# TiltyDuo.net
KiCad netlist of a schematic drawn in EAGLE
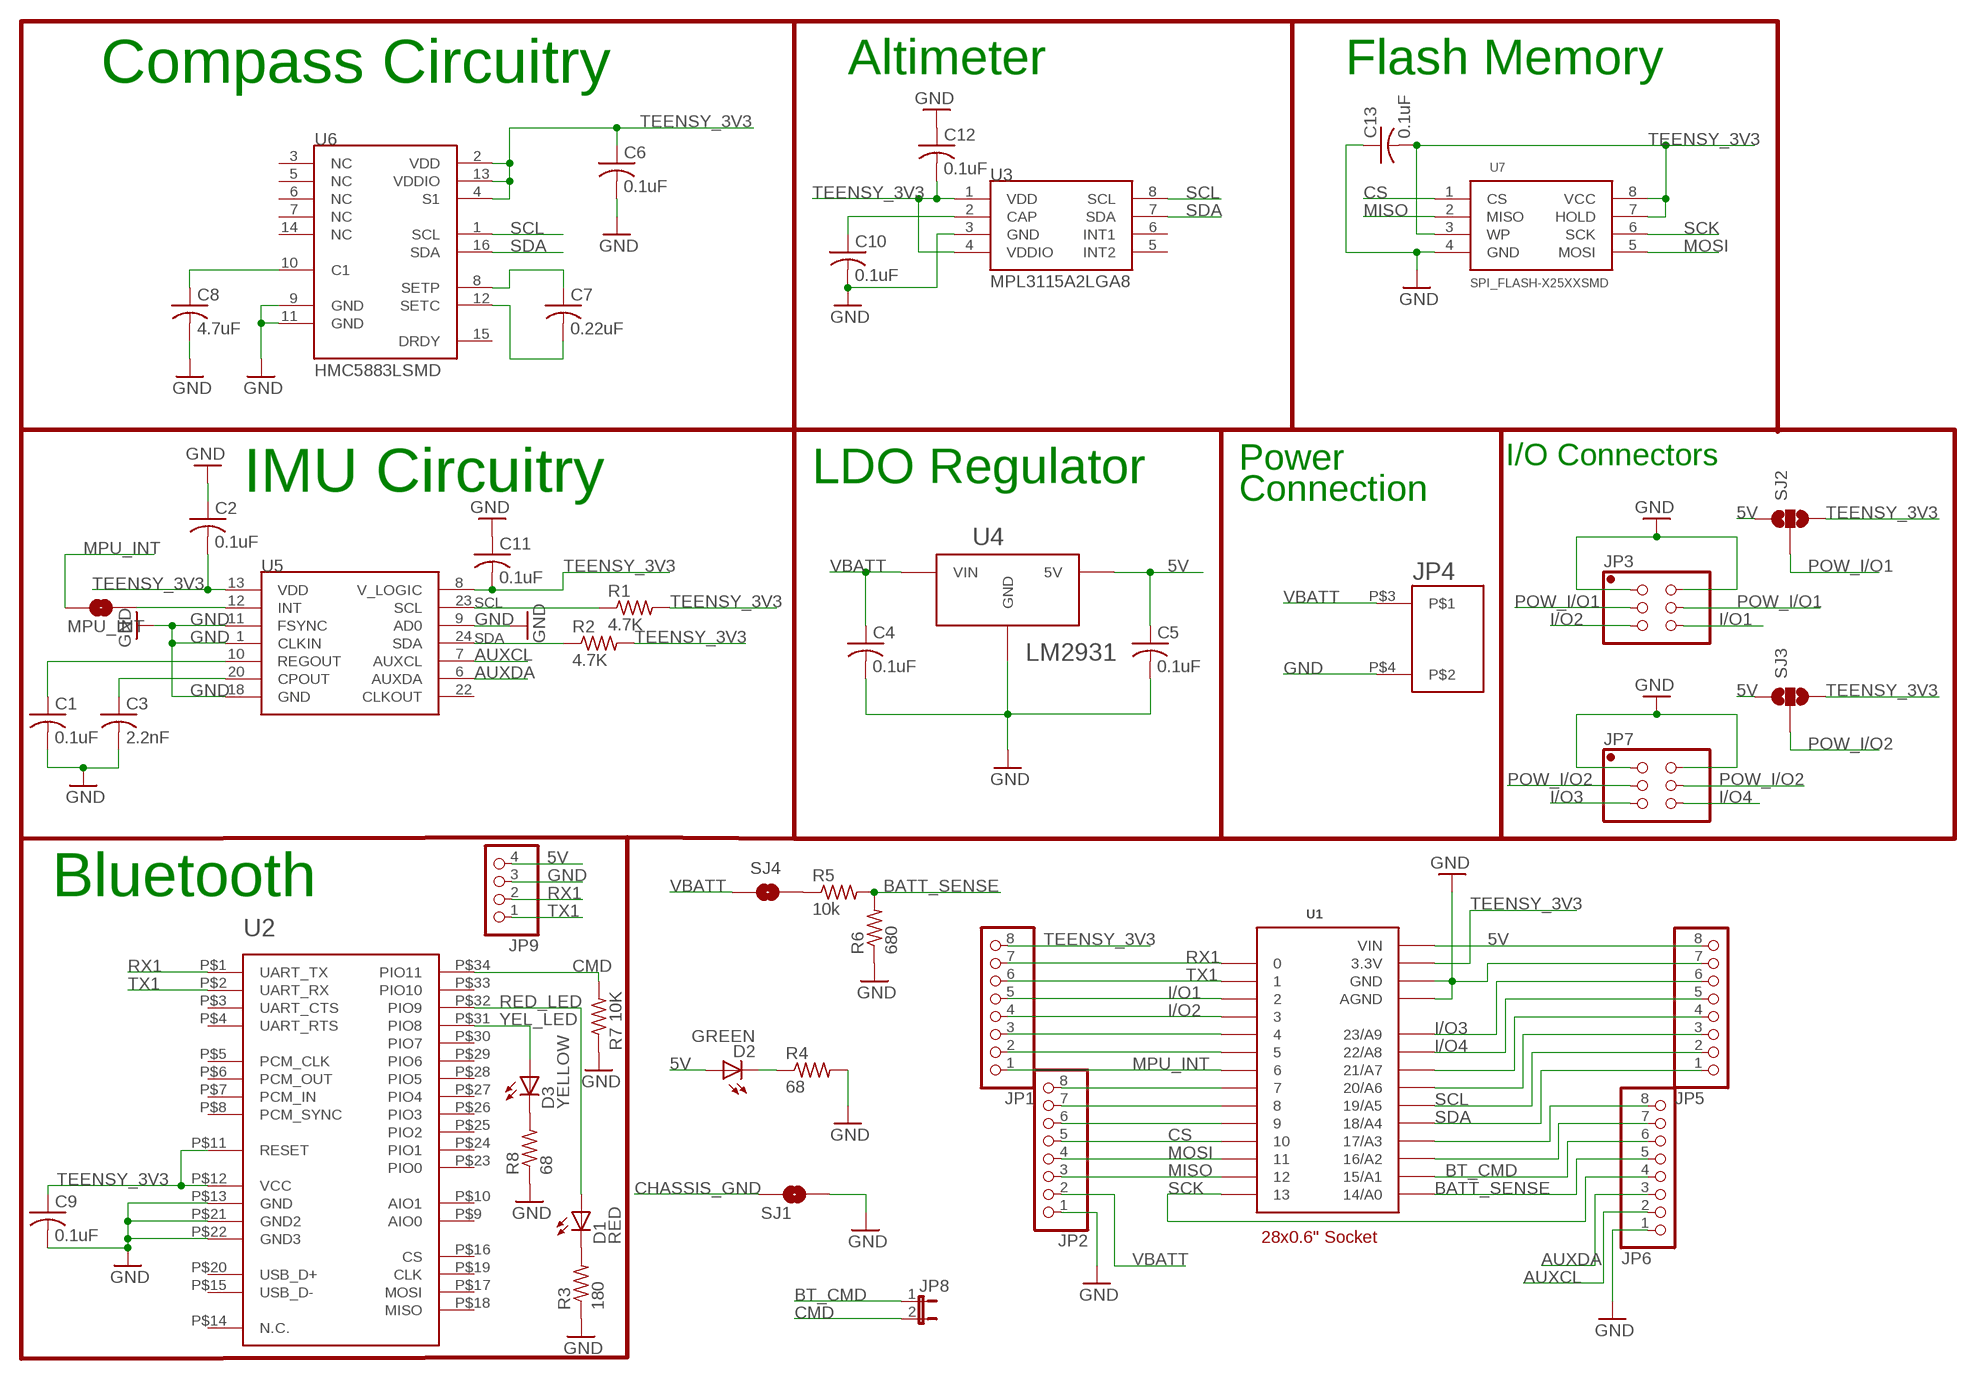
[diagram p0: schematic, sheet 1]

(export (version "E")
  (design (tool "Eeschema 10.0.6"))
  (components
    (comp (ref "C1")
      (value "0.1uF")
      (footprint "eagle-import:C0603")
      (libsource (lib "eagle-import") (part "C-USC0603"))
    )
    (comp (ref "C2")
      (value "0.1uF")
      (footprint "eagle-import:C0603")
      (libsource (lib "eagle-import") (part "C-USC0603"))
    )
    (comp (ref "C3")
      (value "2.2nF")
      (footprint "eagle-import:C0603")
      (libsource (lib "eagle-import") (part "C-USC0603"))
    )
    (comp (ref "C4")
      (value "0.1uF")
      (footprint "eagle-import:C0603")
      (libsource (lib "eagle-import") (part "C-USC0603"))
    )
    (comp (ref "C5")
      (value "0.1uF")
      (footprint "eagle-import:C0603")
      (libsource (lib "eagle-import") (part "C-USC0603"))
    )
    (comp (ref "C6")
      (value "0.1uF")
      (footprint "eagle-import:C0603")
      (libsource (lib "eagle-import") (part "C-USC0603"))
    )
    (comp (ref "C7")
      (value "0.22uF")
      (footprint "eagle-import:C0603")
      (libsource (lib "eagle-import") (part "C-USC0603"))
    )
    (comp (ref "C8")
      (value "4.7uF")
      (footprint "eagle-import:C0603")
      (libsource (lib "eagle-import") (part "C-USC0603"))
    )
    (comp (ref "C9")
      (value "0.1uF")
      (footprint "eagle-import:C0603")
      (libsource (lib "eagle-import") (part "C-USC0603"))
    )
    (comp (ref "C10")
      (value "0.1uF")
      (footprint "eagle-import:C0603")
      (libsource (lib "eagle-import") (part "C-USC0603"))
    )
    (comp (ref "C11")
      (value "0.1uF")
      (footprint "eagle-import:C0603")
      (libsource (lib "eagle-import") (part "C-USC0603"))
    )
    (comp (ref "C12")
      (value "0.1uF")
      (footprint "eagle-import:C0603")
      (libsource (lib "eagle-import") (part "C-USC0603"))
    )
    (comp (ref "C13")
      (value "0.1uF")
      (footprint "eagle-import:C0603")
      (libsource (lib "eagle-import") (part "C-USC0603"))
    )
    (comp (ref "D1")
      (value "RED")
      (footprint "eagle-import:LED-0805")
      (libsource (lib "eagle-import") (part "LED-GREENLED-0805_NO_SILK"))
    )
    (comp (ref "D2")
      (value "GREEN")
      (footprint "eagle-import:LED-0805")
      (libsource (lib "eagle-import") (part "LED-GREENLED-0805_NO_SILK"))
    )
    (comp (ref "D3")
      (value "YELLOW")
      (footprint "eagle-import:LED-0805")
      (libsource (lib "eagle-import") (part "LED-GREENLED-0805_NO_SILK"))
    )
    (comp (ref "JP1")
      (value "PINHD-1X81X08_NO_SILK_LOCK")
      (footprint "eagle-import:1X08_NO_SS_LOCKING")
      (libsource (lib "eagle-import") (part "PINHD-1X81X08_NO_SILK_LOCK"))
    )
    (comp (ref "JP2")
      (value "PINHD-1X81X08_NO_SILK_LOCK")
      (footprint "eagle-import:1X08_NO_SS_LOCKING")
      (libsource (lib "eagle-import") (part "PINHD-1X81X08_NO_SILK_LOCK"))
    )
    (comp (ref "JP3")
      (value "PINHD-2X32X03_NO_SS_LOCK")
      (footprint "eagle-import:2X03_NO_SS_LOCK")
      (libsource (lib "eagle-import") (part "PINHD-2X32X03_NO_SS_LOCK"))
    )
    (comp (ref "JP4")
      (value "2-POS_SMD_TERM_BLOCK")
      (footprint "eagle-import:2-POS_SMD_TERMINAL_BLOCK")
      (libsource (lib "eagle-import") (part "2-POS_SMD_TERM_BLOCK"))
    )
    (comp (ref "JP5")
      (value "PINHD-1X81X08_NO_SILK_LOCK")
      (footprint "eagle-import:1X08_NO_SS_LOCKING")
      (libsource (lib "eagle-import") (part "PINHD-1X81X08_NO_SILK_LOCK"))
    )
    (comp (ref "JP6")
      (value "PINHD-1X81X08_NO_SILK_LOCK")
      (footprint "eagle-import:1X08_NO_SS_LOCKING")
      (libsource (lib "eagle-import") (part "PINHD-1X81X08_NO_SILK_LOCK"))
    )
    (comp (ref "JP7")
      (value "PINHD-2X32X03_NO_SS_LOCK")
      (footprint "eagle-import:2X03_NO_SS_LOCK")
      (libsource (lib "eagle-import") (part "PINHD-2X32X03_NO_SS_LOCK"))
    )
    (comp (ref "JP8")
      (value "JUMPER-2SMD-NC")
      (footprint "eagle-import:SJ_2S")
      (libsource (lib "eagle-import") (part "JUMPER-2SMD-NC"))
    )
    (comp (ref "JP9")
      (value "PINHD-1X41X04_NO_SS_LOCKING")
      (footprint "eagle-import:1X04_NO_SS_LOCKING")
      (libsource (lib "eagle-import") (part "PINHD-1X41X04_NO_SS_LOCKING"))
    )
    (comp (ref "MPU_INT")
      (value "SOLDERJUMPERNO")
      (footprint "eagle-import:SJ_2S-NO")
      (libsource (lib "eagle-import") (part "SOLDERJUMPERNO"))
    )
    (comp (ref "R1")
      (value "4.7K")
      (footprint "eagle-import:R0603")
      (libsource (lib "eagle-import") (part "R-US_R0603"))
    )
    (comp (ref "R2")
      (value "4.7K")
      (footprint "eagle-import:R0603")
      (libsource (lib "eagle-import") (part "R-US_R0603"))
    )
    (comp (ref "R3")
      (value "180")
      (footprint "eagle-import:R0603")
      (libsource (lib "eagle-import") (part "R-US_R0603"))
    )
    (comp (ref "R4")
      (value "68")
      (footprint "eagle-import:R0603")
      (libsource (lib "eagle-import") (part "R-US_R0603"))
    )
    (comp (ref "R5")
      (value "10k")
      (footprint "eagle-import:R0603")
      (libsource (lib "eagle-import") (part "R-US_R0603"))
    )
    (comp (ref "R6")
      (value "680")
      (footprint "eagle-import:R0603")
      (libsource (lib "eagle-import") (part "R-US_R0603"))
    )
    (comp (ref "R7")
      (value "10K")
      (footprint "eagle-import:R0603")
      (libsource (lib "eagle-import") (part "R-US_R0603"))
    )
    (comp (ref "R8")
      (value "68")
      (footprint "eagle-import:R0603")
      (libsource (lib "eagle-import") (part "R-US_R0603"))
    )
    (comp (ref "SJ1")
      (value "SOLDERJUMPERNO")
      (footprint "eagle-import:SJ_2S-NO")
      (libsource (lib "eagle-import") (part "SOLDERJUMPERNO"))
    )
    (comp (ref "SJ2")
      (value "SOLDERJUMPER_2WAYS")
      (footprint "eagle-import:SJ_3")
      (libsource (lib "eagle-import") (part "SOLDERJUMPER_2WAYS"))
    )
    (comp (ref "SJ3")
      (value "SOLDERJUMPER_2WAYS")
      (footprint "eagle-import:SJ_3")
      (libsource (lib "eagle-import") (part "SOLDERJUMPER_2WAYS"))
    )
    (comp (ref "SJ4")
      (value "SOLDERJUMPERTRACE")
      (footprint "eagle-import:SJ_2S-TRACE")
      (libsource (lib "eagle-import") (part "SOLDERJUMPERTRACE"))
    )
    (comp (ref "U1")
      (value "TEENSY_3.0_OUTER-PINS28-DIP_SOCKET")
      (footprint "eagle-import:28-DIP")
      (libsource (lib "eagle-import") (part "TEENSY_3.0_OUTER-PINS28-DIP_SOCKET"))
    )
    (comp (ref "U2")
      (value "HC-09_BREAKOUT")
      (footprint "eagle-import:HC-09_BREAKOUT")
      (libsource (lib "eagle-import") (part "HC-09_BREAKOUT"))
    )
    (comp (ref "U3")
      (value "MPL3115A2LGA8")
      (footprint "eagle-import:LGA8")
      (libsource (lib "eagle-import") (part "MPL3115A2LGA8"))
    )
    (comp (ref "U4")
      (value "LM2931")
      (footprint "eagle-import:TO263")
      (libsource (lib "eagle-import") (part "LM2931"))
    )
    (comp (ref "U5")
      (value "MPU-6050")
      (footprint "eagle-import:QFN-24")
      (libsource (lib "eagle-import") (part "MPU-6050"))
    )
    (comp (ref "U6")
      (value "HMC5883LSMD")
      (footprint "eagle-import:16LPCC")
      (libsource (lib "eagle-import") (part "HMC5883LSMD"))
    )
    (comp (ref "U7")
      (value "SPI_FLASH-X25XXSMD")
      (footprint "eagle-import:SO08")
      (fields (field (name "PART#") "S25FL204K0TMFI011"))
      (libsource (lib "eagle-import") (part "SPI_FLASH-X25XXSMD"))
    )
  )
  (nets
    (net (code "1") (name "/5V") (class "Default")
      (node (ref "C5") (pin "1") (pinfunction "1_1") (pintype "passive"))
      (node (ref "D2") (pin "1") (pinfunction "A_1") (pintype "passive"))
      (node (ref "JP5") (pin "8") (pinfunction "8_8") (pintype "passive"))
      (node (ref "JP9") (pin "4") (pinfunction "4_4") (pintype "passive"))
      (node (ref "SJ2") (pin "1") (pinfunction "1_1") (pintype "passive"))
      (node (ref "SJ3") (pin "1") (pinfunction "1_1") (pintype "passive"))
      (node (ref "U1") (pin "P$15") (pinfunction "VIN_P$15") (pintype "power_in"))
      (node (ref "U4") (pin "P$3") (pinfunction "5V_P$3") (pintype "bidirectional"))
    )
    (net (code "2") (name "/AUXCL") (class "Default")
      (node (ref "JP6") (pin "2") (pinfunction "2_2") (pintype "passive"))
      (node (ref "U5") (pin "7") (pinfunction "AUXCL_7") (pintype "bidirectional"))
    )
    (net (code "3") (name "/AUXDA") (class "Default")
      (node (ref "JP6") (pin "3") (pinfunction "3_3") (pintype "passive"))
      (node (ref "U5") (pin "6") (pinfunction "AUXDA_6") (pintype "bidirectional"))
    )
    (net (code "4") (name "/BATT_SENSE") (class "Default")
      (node (ref "JP6") (pin "5") (pinfunction "5_5") (pintype "passive"))
      (node (ref "R5") (pin "2") (pinfunction "2_2") (pintype "passive"))
      (node (ref "R6") (pin "2") (pinfunction "2_2") (pintype "passive"))
      (node (ref "U1") (pin "P$27") (pinfunction "14/A0_P$27") (pintype "bidirectional"))
    )
    (net (code "5") (name "/BT_CMD") (class "Default")
      (node (ref "JP6") (pin "6") (pinfunction "6_6") (pintype "passive"))
      (node (ref "JP8") (pin "1") (pinfunction "1_1") (pintype "passive"))
      (node (ref "U1") (pin "P$26") (pinfunction "15/A1_P$26") (pintype "bidirectional"))
    )
    (net (code "6") (name "/CHASSIS_GND") (class "Default")
      (node (ref "SJ1") (pin "1") (pinfunction "1_1") (pintype "passive"))
    )
    (net (code "7") (name "/CMD") (class "Default")
      (node (ref "JP8") (pin "2") (pinfunction "2_2") (pintype "passive"))
      (node (ref "R7") (pin "2") (pinfunction "2_2") (pintype "passive"))
      (node (ref "U2") (pin "P$34") (pinfunction "PIO11_P$34") (pintype "bidirectional"))
    )
    (net (code "8") (name "/CS") (class "Default")
      (node (ref "JP2") (pin "5") (pinfunction "5_5") (pintype "passive"))
      (node (ref "U1") (pin "P$12") (pinfunction "10_P$12") (pintype "bidirectional"))
      (node (ref "U7") (pin "1") (pinfunction "CS_1") (pintype "bidirectional"))
    )
    (net (code "9") (name "/I{slash}O1") (class "Default")
      (node (ref "JP1") (pin "5") (pinfunction "5_5") (pintype "passive"))
      (node (ref "JP3") (pin "6") (pinfunction "6_6") (pintype "passive"))
      (node (ref "U1") (pin "P$4") (pinfunction "2_P$4") (pintype "bidirectional"))
    )
    (net (code "10") (name "/I{slash}O2") (class "Default")
      (node (ref "JP1") (pin "4") (pinfunction "4_4") (pintype "passive"))
      (node (ref "JP3") (pin "5") (pinfunction "5_5") (pintype "passive"))
      (node (ref "U1") (pin "P$5") (pinfunction "3_P$5") (pintype "bidirectional"))
    )
    (net (code "11") (name "/I{slash}O3") (class "Default")
      (node (ref "JP5") (pin "6") (pinfunction "6_6") (pintype "passive"))
      (node (ref "JP7") (pin "5") (pinfunction "5_5") (pintype "passive"))
      (node (ref "U1") (pin "P$18") (pinfunction "23/A9_P$18") (pintype "bidirectional"))
    )
    (net (code "12") (name "/I{slash}O4") (class "Default")
      (node (ref "JP5") (pin "5") (pinfunction "5_5") (pintype "passive"))
      (node (ref "JP7") (pin "6") (pinfunction "6_6") (pintype "passive"))
      (node (ref "U1") (pin "P$19") (pinfunction "22/A8_P$19") (pintype "bidirectional"))
    )
    (net (code "13") (name "/MISO") (class "Default")
      (node (ref "JP2") (pin "3") (pinfunction "3_3") (pintype "passive"))
      (node (ref "U1") (pin "P$14") (pinfunction "12_P$14") (pintype "bidirectional"))
      (node (ref "U7") (pin "2") (pinfunction "MISO_2") (pintype "bidirectional"))
    )
    (net (code "14") (name "/MOSI") (class "Default")
      (node (ref "JP2") (pin "4") (pinfunction "4_4") (pintype "passive"))
      (node (ref "U1") (pin "P$13") (pinfunction "11_P$13") (pintype "bidirectional"))
      (node (ref "U7") (pin "5") (pinfunction "MOSI_5") (pintype "bidirectional"))
    )
    (net (code "15") (name "/MPU_INT") (class "Default")
      (node (ref "JP1") (pin "1") (pinfunction "1_1") (pintype "passive"))
      (node (ref "MPU_INT") (pin "1") (pinfunction "1_1") (pintype "passive"))
      (node (ref "U1") (pin "P$8") (pinfunction "6_P$8") (pintype "bidirectional"))
    )
    (net (code "16") (name "/POW_I{slash}O1") (class "Default")
      (node (ref "JP3") (pin "3") (pinfunction "3_3") (pintype "passive"))
      (node (ref "JP3") (pin "4") (pinfunction "4_4") (pintype "passive"))
      (node (ref "SJ2") (pin "2") (pinfunction "2_2") (pintype "passive"))
    )
    (net (code "17") (name "/POW_I{slash}O2") (class "Default")
      (node (ref "JP7") (pin "3") (pinfunction "3_3") (pintype "passive"))
      (node (ref "JP7") (pin "4") (pinfunction "4_4") (pintype "passive"))
      (node (ref "SJ3") (pin "2") (pinfunction "2_2") (pintype "passive"))
    )
    (net (code "18") (name "/RED_LED") (class "Default")
      (node (ref "D1") (pin "1") (pinfunction "A_1") (pintype "passive"))
      (node (ref "U2") (pin "P$32") (pinfunction "PIO9_P$32") (pintype "bidirectional"))
    )
    (net (code "19") (name "/RX1") (class "Default")
      (node (ref "JP1") (pin "7") (pinfunction "7_7") (pintype "passive"))
      (node (ref "JP9") (pin "2") (pinfunction "2_2") (pintype "passive"))
      (node (ref "U1") (pin "P$2") (pinfunction "0_P$2") (pintype "bidirectional"))
      (node (ref "U2") (pin "P$1") (pinfunction "UART_TX_P$1") (pintype "bidirectional"))
    )
    (net (code "20") (name "/SCK") (class "Default")
      (node (ref "JP6") (pin "4") (pinfunction "4_4") (pintype "passive"))
      (node (ref "U1") (pin "P$28") (pinfunction "13_P$28") (pintype "bidirectional"))
      (node (ref "U7") (pin "6") (pinfunction "SCK_6") (pintype "bidirectional"))
    )
    (net (code "21") (name "/SCL") (class "Default")
      (node (ref "JP5") (pin "2") (pinfunction "2_2") (pintype "passive"))
      (node (ref "R1") (pin "1") (pinfunction "1_1") (pintype "passive"))
      (node (ref "U1") (pin "P$22") (pinfunction "19/A5_P$22") (pintype "bidirectional"))
      (node (ref "U3") (pin "8") (pinfunction "SCL_8") (pintype "bidirectional"))
      (node (ref "U5") (pin "23") (pinfunction "SCL_23") (pintype "bidirectional"))
      (node (ref "U6") (pin "1") (pinfunction "SCL_1") (pintype "bidirectional"))
    )
    (net (code "22") (name "/SDA") (class "Default")
      (node (ref "JP5") (pin "1") (pinfunction "1_1") (pintype "passive"))
      (node (ref "R2") (pin "1") (pinfunction "1_1") (pintype "passive"))
      (node (ref "U1") (pin "P$23") (pinfunction "18/A4_P$23") (pintype "bidirectional"))
      (node (ref "U3") (pin "7") (pinfunction "SDA_7") (pintype "bidirectional"))
      (node (ref "U5") (pin "24") (pinfunction "SDA_24") (pintype "bidirectional"))
      (node (ref "U6") (pin "16") (pinfunction "SDA_16") (pintype "bidirectional"))
    )
    (net (code "23") (name "/TEENSY_3V3") (class "Default")
      (node (ref "C11") (pin "2") (pinfunction "2_2") (pintype "passive"))
      (node (ref "C12") (pin "2") (pinfunction "2_2") (pintype "passive"))
      (node (ref "C13") (pin "2") (pinfunction "2_2") (pintype "passive"))
      (node (ref "C2") (pin "2") (pinfunction "2_2") (pintype "passive"))
      (node (ref "C6") (pin "1") (pinfunction "1_1") (pintype "passive"))
      (node (ref "C9") (pin "1") (pinfunction "1_1") (pintype "passive"))
      (node (ref "JP1") (pin "8") (pinfunction "8_8") (pintype "passive"))
      (node (ref "R1") (pin "2") (pinfunction "2_2") (pintype "passive"))
      (node (ref "R2") (pin "2") (pinfunction "2_2") (pintype "passive"))
      (node (ref "SJ2") (pin "3") (pinfunction "3_3") (pintype "passive"))
      (node (ref "SJ3") (pin "3") (pinfunction "3_3") (pintype "passive"))
      (node (ref "U1") (pin "P$17") (pinfunction "3.3V_P$17") (pintype "power_in"))
      (node (ref "U2") (pin "P$11") (pinfunction "RESET_P$11") (pintype "bidirectional"))
      (node (ref "U2") (pin "P$12") (pinfunction "VCC_P$12") (pintype "bidirectional"))
      (node (ref "U3") (pin "1") (pinfunction "VDD_1") (pintype "bidirectional"))
      (node (ref "U3") (pin "4") (pinfunction "VDDIO_4") (pintype "bidirectional"))
      (node (ref "U5") (pin "13") (pinfunction "VDD_13") (pintype "bidirectional"))
      (node (ref "U5") (pin "8") (pinfunction "V_LOGIC_8") (pintype "bidirectional"))
      (node (ref "U6") (pin "13") (pinfunction "VDDIO_13") (pintype "bidirectional"))
      (node (ref "U6") (pin "2") (pinfunction "VDD_2") (pintype "bidirectional"))
      (node (ref "U6") (pin "4") (pinfunction "S1_4") (pintype "bidirectional"))
      (node (ref "U7") (pin "3") (pinfunction "WP_3") (pintype "bidirectional"))
      (node (ref "U7") (pin "7") (pinfunction "HOLD_7") (pintype "bidirectional"))
      (node (ref "U7") (pin "8") (pinfunction "VCC_8") (pintype "bidirectional"))
    )
    (net (code "24") (name "/TX1") (class "Default")
      (node (ref "JP1") (pin "6") (pinfunction "6_6") (pintype "passive"))
      (node (ref "JP9") (pin "1") (pinfunction "1_1") (pintype "passive"))
      (node (ref "U1") (pin "P$3") (pinfunction "1_P$3") (pintype "bidirectional"))
      (node (ref "U2") (pin "P$2") (pinfunction "UART_RX_P$2") (pintype "bidirectional"))
    )
    (net (code "25") (name "/VBATT") (class "Default")
      (node (ref "C4") (pin "1") (pinfunction "1_1") (pintype "passive"))
      (node (ref "JP2") (pin "2") (pinfunction "2_2") (pintype "passive"))
      (node (ref "JP4") (pin "P$3") (pinfunction "P$1_P$3") (pintype "bidirectional"))
      (node (ref "SJ4") (pin "1") (pinfunction "1_1") (pintype "passive"))
      (node (ref "U4") (pin "P$2") (pinfunction "VIN_P$2") (pintype "bidirectional"))
    )
    (net (code "26") (name "/YEL_LED") (class "Default")
      (node (ref "D3") (pin "1") (pinfunction "A_1") (pintype "passive"))
      (node (ref "U2") (pin "P$31") (pinfunction "PIO8_P$31") (pintype "bidirectional"))
    )
    (net (code "27") (name "GND") (class "Default")
      (node (ref "C1") (pin "2") (pinfunction "2_2") (pintype "passive"))
      (node (ref "C10") (pin "2") (pinfunction "2_2") (pintype "passive"))
      (node (ref "C11") (pin "1") (pinfunction "1_1") (pintype "passive"))
      (node (ref "C12") (pin "1") (pinfunction "1_1") (pintype "passive"))
      (node (ref "C13") (pin "1") (pinfunction "1_1") (pintype "passive"))
      (node (ref "C2") (pin "1") (pinfunction "1_1") (pintype "passive"))
      (node (ref "C3") (pin "2") (pinfunction "2_2") (pintype "passive"))
      (node (ref "C4") (pin "2") (pinfunction "2_2") (pintype "passive"))
      (node (ref "C5") (pin "2") (pinfunction "2_2") (pintype "passive"))
      (node (ref "C6") (pin "2") (pinfunction "2_2") (pintype "passive"))
      (node (ref "C8") (pin "2") (pinfunction "2_2") (pintype "passive"))
      (node (ref "C9") (pin "2") (pinfunction "2_2") (pintype "passive"))
      (node (ref "JP2") (pin "1") (pinfunction "1_1") (pintype "passive"))
      (node (ref "JP3") (pin "1") (pinfunction "1_1") (pintype "passive"))
      (node (ref "JP3") (pin "2") (pinfunction "2_2") (pintype "passive"))
      (node (ref "JP4") (pin "P$4") (pinfunction "P$2_P$4") (pintype "bidirectional"))
      (node (ref "JP5") (pin "7") (pinfunction "7_7") (pintype "passive"))
      (node (ref "JP6") (pin "1") (pinfunction "1_1") (pintype "passive"))
      (node (ref "JP7") (pin "1") (pinfunction "1_1") (pintype "passive"))
      (node (ref "JP7") (pin "2") (pinfunction "2_2") (pintype "passive"))
      (node (ref "JP9") (pin "3") (pinfunction "3_3") (pintype "passive"))
      (node (ref "R3") (pin "1") (pinfunction "1_1") (pintype "passive"))
      (node (ref "R4") (pin "2") (pinfunction "2_2") (pintype "passive"))
      (node (ref "R6") (pin "1") (pinfunction "1_1") (pintype "passive"))
      (node (ref "R7") (pin "1") (pinfunction "1_1") (pintype "passive"))
      (node (ref "R8") (pin "1") (pinfunction "1_1") (pintype "passive"))
      (node (ref "SJ1") (pin "2") (pinfunction "2_2") (pintype "passive"))
      (node (ref "U1") (pin "P$1") (pinfunction "GND_P$1") (pintype "power_in"))
      (node (ref "U1") (pin "P$16") (pinfunction "AGND_P$16") (pintype "power_in"))
      (node (ref "U2") (pin "P$13") (pinfunction "GND_P$13") (pintype "bidirectional"))
      (node (ref "U2") (pin "P$21") (pinfunction "GND2_P$21") (pintype "bidirectional"))
      (node (ref "U2") (pin "P$22") (pinfunction "GND3_P$22") (pintype "bidirectional"))
      (node (ref "U3") (pin "3") (pinfunction "GND_3") (pintype "bidirectional"))
      (node (ref "U4") (pin "P$1") (pinfunction "GND_P$1") (pintype "bidirectional"))
      (node (ref "U5") (pin "1") (pinfunction "CLKIN_1") (pintype "bidirectional"))
      (node (ref "U5") (pin "11") (pinfunction "FSYNC_11") (pintype "bidirectional"))
      (node (ref "U5") (pin "18") (pinfunction "GND_18") (pintype "bidirectional"))
      (node (ref "U5") (pin "9") (pinfunction "AD0_9") (pintype "bidirectional"))
      (node (ref "U6") (pin "11") (pinfunction "GND_11") (pintype "bidirectional"))
      (node (ref "U6") (pin "9") (pinfunction "GND_9") (pintype "bidirectional"))
      (node (ref "U7") (pin "4") (pinfunction "GND_4") (pintype "bidirectional"))
    )
    (net (code "28") (name "Net-(D1-C)") (class "Default")
      (node (ref "D1") (pin "2") (pinfunction "C_2") (pintype "passive"))
      (node (ref "R3") (pin "2") (pinfunction "2_2") (pintype "passive"))
    )
    (net (code "29") (name "Net-(D2-C)") (class "Default")
      (node (ref "D2") (pin "2") (pinfunction "C_2") (pintype "passive"))
      (node (ref "R4") (pin "1") (pinfunction "1_1") (pintype "passive"))
    )
    (net (code "30") (name "Net-(D3-C)") (class "Default")
      (node (ref "D3") (pin "2") (pinfunction "C_2") (pintype "passive"))
      (node (ref "R8") (pin "2") (pinfunction "2_2") (pintype "passive"))
    )
    (net (code "31") (name "Net-(R5-Pad1)") (class "Default")
      (node (ref "R5") (pin "1") (pinfunction "1_1") (pintype "passive"))
      (node (ref "SJ4") (pin "2") (pinfunction "2_2") (pintype "passive"))
    )
    (net (code "32") (name "Net-(U1-4)") (class "Default")
      (node (ref "JP1") (pin "3") (pinfunction "3_3") (pintype "passive"))
      (node (ref "U1") (pin "P$6") (pinfunction "4_P$6") (pintype "bidirectional"))
    )
    (net (code "33") (name "Net-(U1-5)") (class "Default")
      (node (ref "JP1") (pin "2") (pinfunction "2_2") (pintype "passive"))
      (node (ref "U1") (pin "P$7") (pinfunction "5_P$7") (pintype "bidirectional"))
    )
    (net (code "34") (name "Net-(U1-7)") (class "Default")
      (node (ref "JP2") (pin "8") (pinfunction "8_8") (pintype "passive"))
      (node (ref "U1") (pin "P$9") (pinfunction "7_P$9") (pintype "bidirectional"))
    )
    (net (code "35") (name "Net-(U1-8)") (class "Default")
      (node (ref "JP2") (pin "7") (pinfunction "7_7") (pintype "passive"))
      (node (ref "U1") (pin "P$10") (pinfunction "8_P$10") (pintype "bidirectional"))
    )
    (net (code "36") (name "Net-(U1-9)") (class "Default")
      (node (ref "JP2") (pin "6") (pinfunction "6_6") (pintype "passive"))
      (node (ref "U1") (pin "P$11") (pinfunction "9_P$11") (pintype "bidirectional"))
    )
    (net (code "37") (name "Net-(U1-16{slash}A2)") (class "Default")
      (node (ref "JP6") (pin "7") (pinfunction "7_7") (pintype "passive"))
      (node (ref "U1") (pin "P$25") (pinfunction "16/A2_P$25") (pintype "bidirectional"))
    )
    (net (code "38") (name "Net-(U1-17{slash}A3)") (class "Default")
      (node (ref "JP6") (pin "8") (pinfunction "8_8") (pintype "passive"))
      (node (ref "U1") (pin "P$24") (pinfunction "17/A3_P$24") (pintype "bidirectional"))
    )
    (net (code "39") (name "Net-(U1-20{slash}A6)") (class "Default")
      (node (ref "JP5") (pin "3") (pinfunction "3_3") (pintype "passive"))
      (node (ref "U1") (pin "P$21") (pinfunction "20/A6_P$21") (pintype "bidirectional"))
    )
    (net (code "40") (name "Net-(U1-21{slash}A7)") (class "Default")
      (node (ref "JP5") (pin "4") (pinfunction "4_4") (pintype "passive"))
      (node (ref "U1") (pin "P$20") (pinfunction "21/A7_P$20") (pintype "bidirectional"))
    )
    (net (code "41") (name "Net-(U3-CAP)") (class "Default")
      (node (ref "C10") (pin "1") (pinfunction "1_1") (pintype "passive"))
      (node (ref "U3") (pin "2") (pinfunction "CAP_2") (pintype "bidirectional"))
    )
    (net (code "42") (name "Net-(U5-CPOUT)") (class "Default")
      (node (ref "C3") (pin "1") (pinfunction "1_1") (pintype "passive"))
      (node (ref "U5") (pin "20") (pinfunction "CPOUT_20") (pintype "bidirectional"))
    )
    (net (code "43") (name "Net-(U5-INT)") (class "Default")
      (node (ref "MPU_INT") (pin "2") (pinfunction "2_2") (pintype "passive"))
      (node (ref "U5") (pin "12") (pinfunction "INT_12") (pintype "bidirectional"))
    )
    (net (code "44") (name "Net-(U5-REGOUT)") (class "Default")
      (node (ref "C1") (pin "1") (pinfunction "1_1") (pintype "passive"))
      (node (ref "U5") (pin "10") (pinfunction "REGOUT_10") (pintype "bidirectional"))
    )
    (net (code "45") (name "Net-(U6-C1)") (class "Default")
      (node (ref "C8") (pin "1") (pinfunction "1_1") (pintype "passive"))
      (node (ref "U6") (pin "10") (pinfunction "C1_10") (pintype "bidirectional"))
    )
    (net (code "46") (name "Net-(U6-SETC)") (class "Default")
      (node (ref "C7") (pin "2") (pinfunction "2_2") (pintype "passive"))
      (node (ref "U6") (pin "12") (pinfunction "SETC_12") (pintype "bidirectional"))
    )
    (net (code "47") (name "Net-(U6-SETP)") (class "Default")
      (node (ref "C7") (pin "1") (pinfunction "1_1") (pintype "passive"))
      (node (ref "U6") (pin "8") (pinfunction "SETP_8") (pintype "bidirectional"))
    )
    (net (code "48") (name "unconnected-(U2-AIO0-PadP$9)") (class "Default")
      (node (ref "U2") (pin "P$9") (pinfunction "AIO0_P$9") (pintype "bidirectional"))
    )
    (net (code "49") (name "unconnected-(U2-AIO1-PadP$10)") (class "Default")
      (node (ref "U2") (pin "P$10") (pinfunction "AIO1_P$10") (pintype "bidirectional"))
    )
    (net (code "50") (name "unconnected-(U2-CLK-PadP$19)") (class "Default")
      (node (ref "U2") (pin "P$19") (pinfunction "CLK_P$19") (pintype "bidirectional"))
    )
    (net (code "51") (name "unconnected-(U2-CS-PadP$16)") (class "Default")
      (node (ref "U2") (pin "P$16") (pinfunction "CS_P$16") (pintype "bidirectional"))
    )
    (net (code "52") (name "unconnected-(U2-MISO-PadP$18)") (class "Default")
      (node (ref "U2") (pin "P$18") (pinfunction "MISO_P$18") (pintype "bidirectional"))
    )
    (net (code "53") (name "unconnected-(U2-MOSI-PadP$17)") (class "Default")
      (node (ref "U2") (pin "P$17") (pinfunction "MOSI_P$17") (pintype "bidirectional"))
    )
    (net (code "54") (name "unconnected-(U2-N.C.-PadP$14)") (class "Default")
      (node (ref "U2") (pin "P$14") (pinfunction "N.C._P$14") (pintype "bidirectional"))
    )
    (net (code "55") (name "unconnected-(U2-PCM_CLK-PadP$5)") (class "Default")
      (node (ref "U2") (pin "P$5") (pinfunction "PCM_CLK_P$5") (pintype "bidirectional"))
    )
    (net (code "56") (name "unconnected-(U2-PCM_IN-PadP$7)") (class "Default")
      (node (ref "U2") (pin "P$7") (pinfunction "PCM_IN_P$7") (pintype "bidirectional"))
    )
    (net (code "57") (name "unconnected-(U2-PCM_OUT-PadP$6)") (class "Default")
      (node (ref "U2") (pin "P$6") (pinfunction "PCM_OUT_P$6") (pintype "bidirectional"))
    )
    (net (code "58") (name "unconnected-(U2-PCM_SYNC-PadP$8)") (class "Default")
      (node (ref "U2") (pin "P$8") (pinfunction "PCM_SYNC_P$8") (pintype "bidirectional"))
    )
    (net (code "59") (name "unconnected-(U2-PIO0-PadP$23)") (class "Default")
      (node (ref "U2") (pin "P$23") (pinfunction "PIO0_P$23") (pintype "bidirectional"))
    )
    (net (code "60") (name "unconnected-(U2-PIO1-PadP$24)") (class "Default")
      (node (ref "U2") (pin "P$24") (pinfunction "PIO1_P$24") (pintype "bidirectional"))
    )
    (net (code "61") (name "unconnected-(U2-PIO2-PadP$25)") (class "Default")
      (node (ref "U2") (pin "P$25") (pinfunction "PIO2_P$25") (pintype "bidirectional"))
    )
    (net (code "62") (name "unconnected-(U2-PIO3-PadP$26)") (class "Default")
      (node (ref "U2") (pin "P$26") (pinfunction "PIO3_P$26") (pintype "bidirectional"))
    )
    (net (code "63") (name "unconnected-(U2-PIO4-PadP$27)") (class "Default")
      (node (ref "U2") (pin "P$27") (pinfunction "PIO4_P$27") (pintype "bidirectional"))
    )
    (net (code "64") (name "unconnected-(U2-PIO5-PadP$28)") (class "Default")
      (node (ref "U2") (pin "P$28") (pinfunction "PIO5_P$28") (pintype "bidirectional"))
    )
    (net (code "65") (name "unconnected-(U2-PIO6-PadP$29)") (class "Default")
      (node (ref "U2") (pin "P$29") (pinfunction "PIO6_P$29") (pintype "bidirectional"))
    )
    (net (code "66") (name "unconnected-(U2-PIO7-PadP$30)") (class "Default")
      (node (ref "U2") (pin "P$30") (pinfunction "PIO7_P$30") (pintype "bidirectional"))
    )
    (net (code "67") (name "unconnected-(U2-PIO10-PadP$33)") (class "Default")
      (node (ref "U2") (pin "P$33") (pinfunction "PIO10_P$33") (pintype "bidirectional"))
    )
    (net (code "68") (name "unconnected-(U2-UART_CTS-PadP$3)") (class "Default")
      (node (ref "U2") (pin "P$3") (pinfunction "UART_CTS_P$3") (pintype "bidirectional"))
    )
    (net (code "69") (name "unconnected-(U2-UART_RTS-PadP$4)") (class "Default")
      (node (ref "U2") (pin "P$4") (pinfunction "UART_RTS_P$4") (pintype "bidirectional"))
    )
    (net (code "70") (name "unconnected-(U2-USB_D+-PadP$20)") (class "Default")
      (node (ref "U2") (pin "P$20") (pinfunction "USB_D+_P$20") (pintype "bidirectional"))
    )
    (net (code "71") (name "unconnected-(U2-USB_D--PadP$15)") (class "Default")
      (node (ref "U2") (pin "P$15") (pinfunction "USB_D-_P$15") (pintype "bidirectional"))
    )
    (net (code "72") (name "unconnected-(U3-INT1-Pad6)") (class "Default")
      (node (ref "U3") (pin "6") (pinfunction "INT1_6") (pintype "bidirectional"))
    )
    (net (code "73") (name "unconnected-(U3-INT2-Pad5)") (class "Default")
      (node (ref "U3") (pin "5") (pinfunction "INT2_5") (pintype "bidirectional"))
    )
    (net (code "74") (name "unconnected-(U5-CLKOUT-Pad22)") (class "Default")
      (node (ref "U5") (pin "22") (pinfunction "CLKOUT_22") (pintype "bidirectional"))
    )
    (net (code "75") (name "unconnected-(U6-DRDY-Pad15)") (class "Default")
      (node (ref "U6") (pin "15") (pinfunction "DRDY_15") (pintype "bidirectional"))
    )
    (net (code "76") (name "unconnected-(U6-NC-Pad3)") (class "Default")
      (node (ref "U6") (pin "3") (pinfunction "NC_3") (pintype "bidirectional"))
    )
    (net (code "77") (name "unconnected-(U6-NC-Pad5)") (class "Default")
      (node (ref "U6") (pin "5") (pinfunction "NC_5") (pintype "bidirectional"))
    )
    (net (code "78") (name "unconnected-(U6-NC-Pad6)") (class "Default")
      (node (ref "U6") (pin "6") (pinfunction "NC_6") (pintype "bidirectional"))
    )
    (net (code "79") (name "unconnected-(U6-NC-Pad7)") (class "Default")
      (node (ref "U6") (pin "7") (pinfunction "NC_7") (pintype "bidirectional"))
    )
    (net (code "80") (name "unconnected-(U6-NC-Pad14)") (class "Default")
      (node (ref "U6") (pin "14") (pinfunction "NC_14") (pintype "bidirectional"))
    )
  )
)
